# 2018_ACT_EXPANDER.net
KiCad netlist of a schematic drawn in Altium Designer
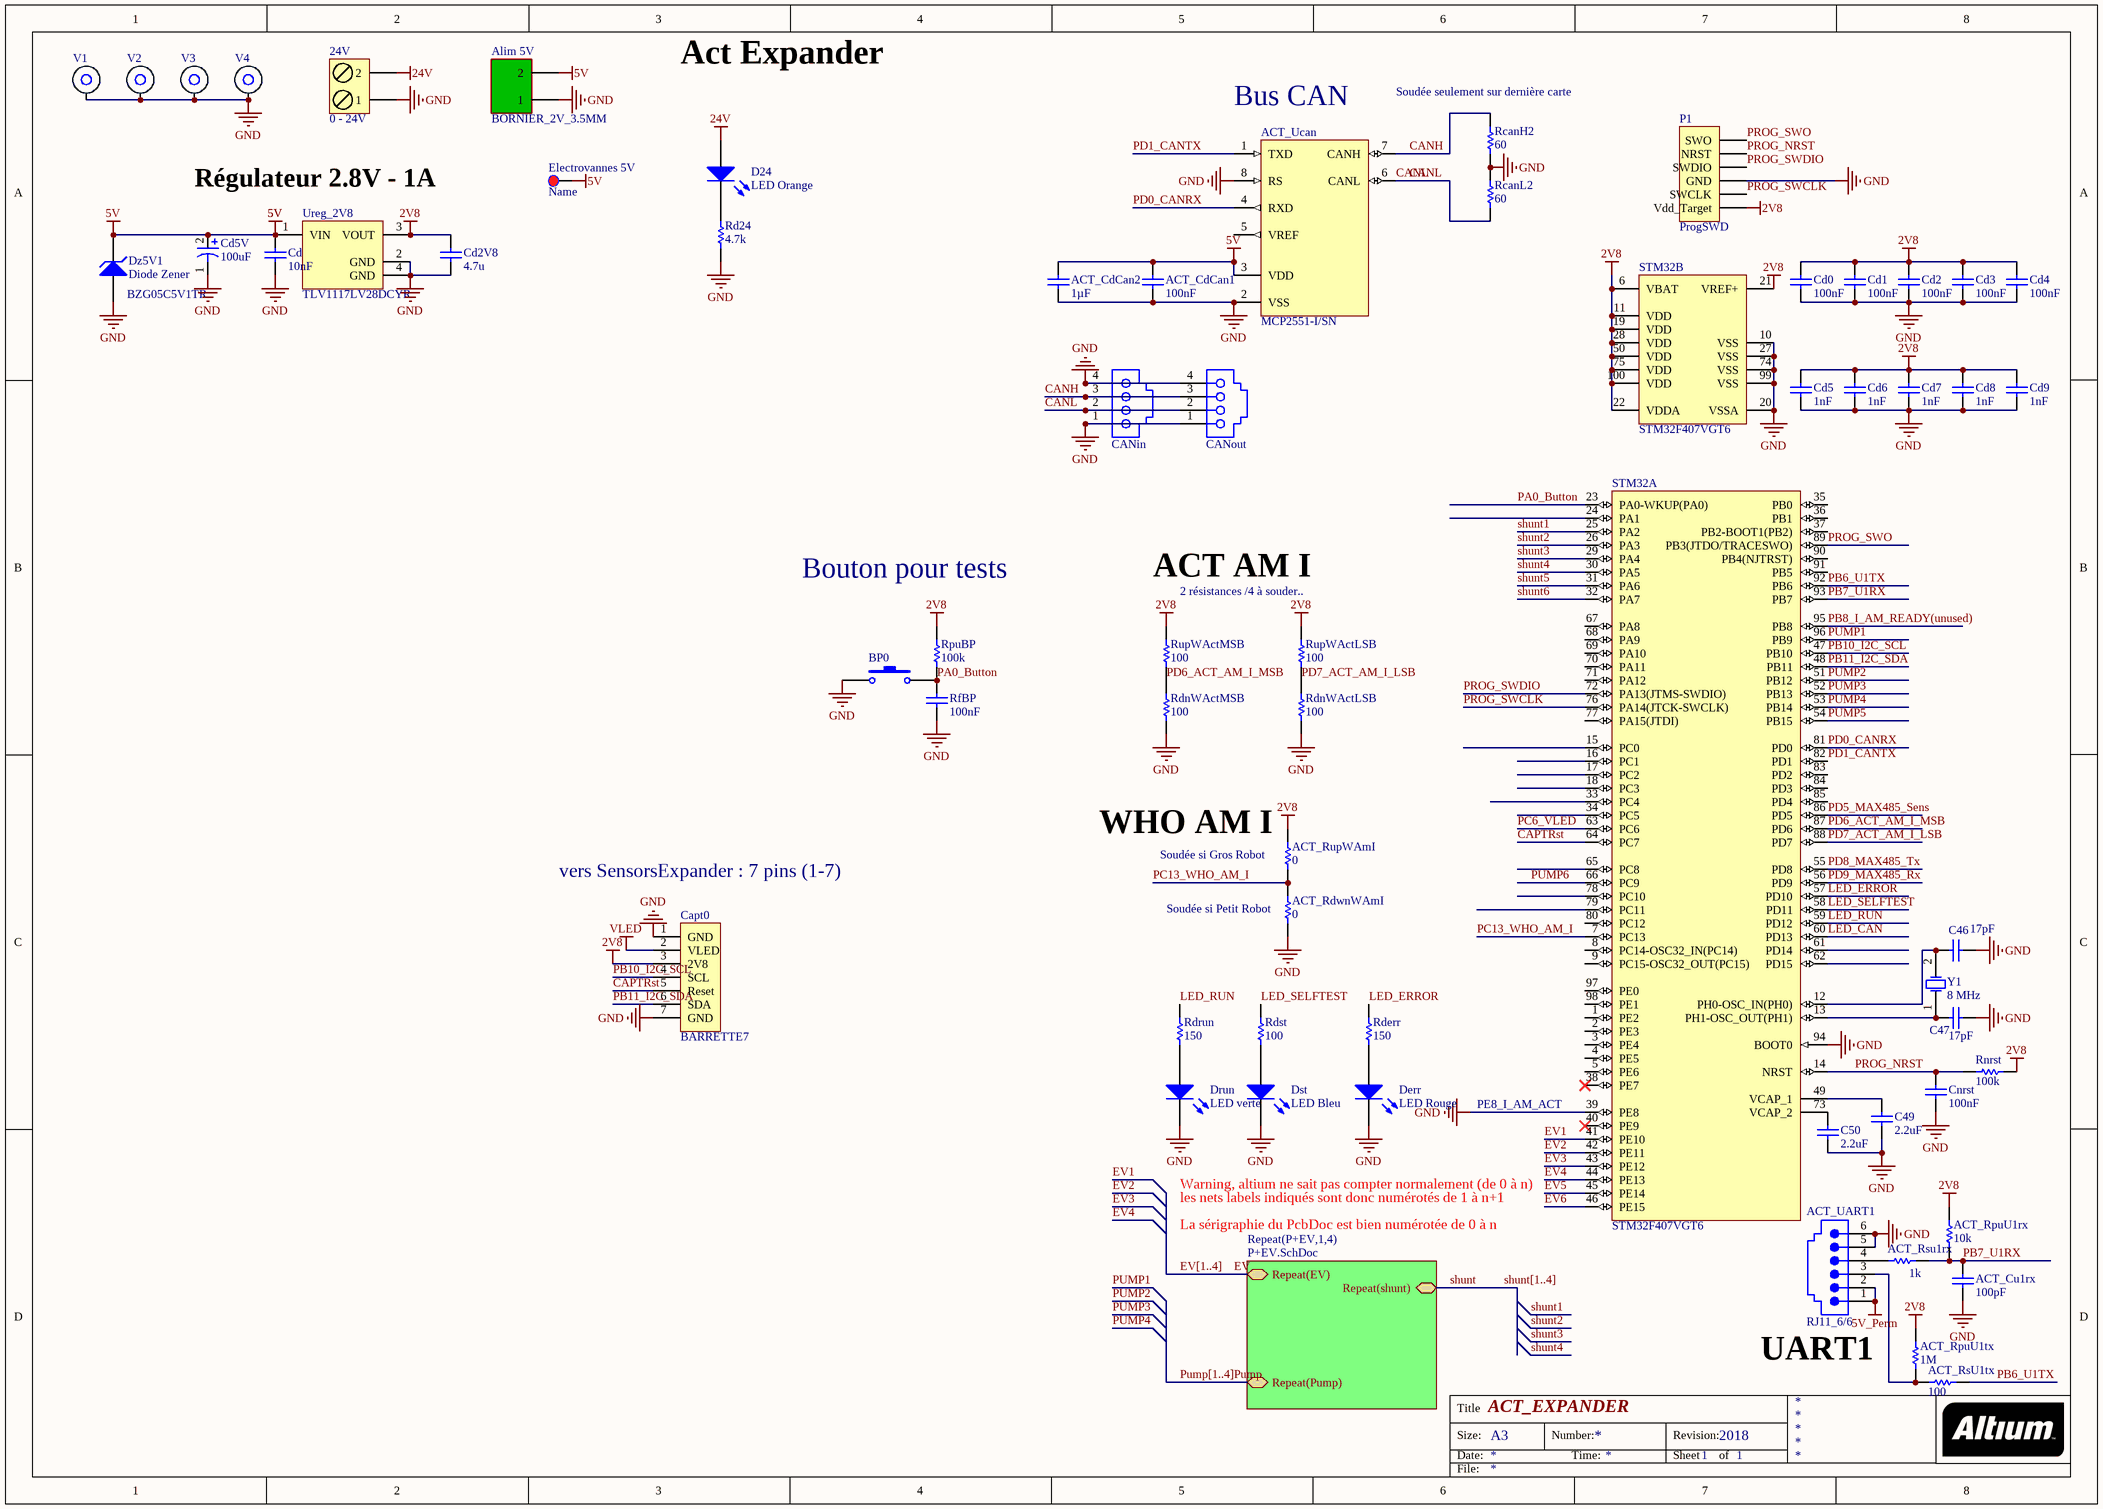
[diagram p0: 2018_ACT_EXPANDER.SchDoc]

(export (version "E")
  (design (tool "Eeschema 10.0.6"))
  (components
    (comp (ref "24V")
      (value "0 - 24V")
      (footprint "BORNIER2_FEM_COUDE")
      (description "Terminal blocks, 2 pins, pitch=5mm")
      (libsource (lib "miniprojet") (part "BORNIER2"))
    )
    (comp (ref "ACT_CdCan1")
      (value "100nF")
      (footprint "C0805_N")
      (description "Capacitor")
      (fields (field (name "PUBLISHER") "Altium Limited"))
      (libsource (lib "_ROBOT") (part "Condensateur"))
    )
    (comp (ref "ACT_CdCan2")
      (value "1µF")
      (footprint "C0805_N")
      (description "Capacitor")
      (fields (field (name "PUBLISHER") "Altium Limited"))
      (libsource (lib "_ROBOT") (part "Condensateur"))
    )
    (comp (ref "ACT_Cu1rx")
      (value "100pF")
      (footprint "C0805_N")
      (description "Capacitor")
      (fields (field (name "PUBLISHER") "Altium Limited"))
      (libsource (lib "_ROBOT") (part "Condensateur"))
    )
    (comp (ref "ACT_RdwnWAmI")
      (value "0")
      (footprint "R1206_N")
      (description "Resistor")
      (fields (field (name "PUBLISHER") "Altium Limited"))
      (libsource (lib "_ROBOT") (part "Resistor"))
    )
    (comp (ref "ACT_RpuU1rx")
      (value "10k")
      (footprint "R1206_N")
      (description "Resistor")
      (fields (field (name "PUBLISHER") "Altium Limited"))
      (libsource (lib "_ROBOT") (part "Resistor"))
    )
    (comp (ref "ACT_RpuU1tx")
      (value "1M")
      (footprint "R1206_N")
      (description "Resistor")
      (fields (field (name "PUBLISHER") "Altium Limited"))
      (libsource (lib "_ROBOT") (part "Resistor"))
    )
    (comp (ref "ACT_Rsu1rx")
      (value "1k")
      (footprint "R1206_N")
      (description "Resistor")
      (fields (field (name "PUBLISHER") "Altium Limited"))
      (libsource (lib "_ROBOT") (part "Resistor"))
    )
    (comp (ref "ACT_RsU1tx")
      (value "100")
      (footprint "R1206_N")
      (description "Resistor")
      (fields (field (name "PUBLISHER") "Altium Limited"))
      (libsource (lib "_ROBOT") (part "Resistor"))
    )
    (comp (ref "ACT_RupWAmI")
      (value "0")
      (footprint "R1206_N")
      (description "Resistor")
      (fields (field (name "PUBLISHER") "Altium Limited"))
      (libsource (lib "_ROBOT") (part "Resistor"))
    )
    (comp (ref "ACT_UART1")
      (value "RJ11_6/6")
      (footprint "RJ11_6/6 - droit")
      (description "Right Angle, Standard Profile, Offset Latch DECconnect, Flangeless PCB Jack")
      (fields (field (name "PUBLISHER") "Altium Limited"))
      (libsource (lib "Connecteur") (part "RJ11_6/6"))
    )
    (comp (ref "ACT_Ucan")
      (value "MCP2551-I/SN")
      (footprint "SO8_N")
      (description "High-Speed CAN Transceiver, 8-Pin SOIC, Industrial Temperature")
      (fields (field (name "PUBLISHER") "Damien Guitton"))
      (libsource (lib "Circuit intégré") (part "MCP2551-I/SN"))
    )
    (comp (ref "Alim 5V")
      (value "BORNIER_2V_3.5MM")
      (footprint "BORNIER_2V_3.5MM")
      (libsource (lib "Connecteur") (part "BORNIER_2V_3.5MM"))
    )
    (comp (ref "BP0")
      (value "SW_Pushbutton_6x6mm_Vertical")
      (footprint "Switch 6x6 Vertical")
      (description "Switch tactil 6mm x 6mm Vertical")
      (fields (field (name "PUBLISHER") "Damien Guitton"))
      (libsource (lib "_ROBOT") (part "SW_Pushbutton_6x6mm_Vertical"))
    )
    (comp (ref "C46")
      (value "17pF")
      (footprint "C0805_N")
      (description "Capacitor")
      (fields (field (name "PUBLISHER") "Altium Limited"))
      (libsource (lib "_ROBOT") (part "Condensateur"))
    )
    (comp (ref "C47")
      (value "17pF")
      (footprint "C0805_N")
      (description "Capacitor")
      (fields (field (name "PUBLISHER") "Altium Limited"))
      (libsource (lib "_ROBOT") (part "Condensateur"))
    )
    (comp (ref "C49")
      (value "2.2uF")
      (footprint "C0805_N")
      (description "Capacitor")
      (fields (field (name "PUBLISHER") "Altium Limited"))
      (libsource (lib "_ROBOT") (part "Condensateur"))
    )
    (comp (ref "C50")
      (value "2.2uF")
      (footprint "C0805_N")
      (description "Capacitor")
      (fields (field (name "PUBLISHER") "Altium Limited"))
      (libsource (lib "_ROBOT") (part "Condensateur"))
    )
    (comp (ref "CANin")
      (value "634104149621")
      (footprint "634104149621")
      (description "Modular Jack SMT Vertical Plastic 4P4C Top Entry WR-MJ")
      (fields (field (name "PUBLISHER") "Wurth Elektronik"))
      (libsource (lib "ALTIUM-MJ_VERTICAL_PLASTIC") (part "634104149621"))
    )
    (comp (ref "CANout")
      (value "634104149621")
      (footprint "634104149621")
      (description "Modular Jack SMT Vertical Plastic 4P4C Top Entry WR-MJ")
      (fields (field (name "PUBLISHER") "Wurth Elektronik"))
      (libsource (lib "ALTIUM-MJ_VERTICAL_PLASTIC") (part "634104149621"))
    )
    (comp (ref "Capt0")
      (value "BARRETTE7")
      (footprint "MOLEX7_2.50MM")
      (description "Header, 6-Pin")
      (fields (field (name "PUBLISHER") "Altium Limited"))
      (libsource (lib "Connecteur") (part "BARRETTE7"))
    )
    (comp (ref "Cd")
      (value "10nF")
      (footprint "C0805_N")
      (description "Capacitor")
      (fields (field (name "PUBLISHER") "Altium Limited"))
      (libsource (lib "_ROBOT") (part "Condensateur"))
    )
    (comp (ref "Cd0")
      (value "100nF")
      (footprint "C0805_N")
      (description "Capacitor")
      (fields (field (name "PUBLISHER") "Altium Limited"))
      (libsource (lib "_ROBOT") (part "Condensateur"))
    )
    (comp (ref "Cd1")
      (value "100nF")
      (footprint "C0805_N")
      (description "Capacitor")
      (fields (field (name "PUBLISHER") "Altium Limited"))
      (libsource (lib "_ROBOT") (part "Condensateur"))
    )
    (comp (ref "Cd2")
      (value "100nF")
      (footprint "C0805_N")
      (description "Capacitor")
      (fields (field (name "PUBLISHER") "Altium Limited"))
      (libsource (lib "_ROBOT") (part "Condensateur"))
    )
    (comp (ref "Cd2V8")
      (value "4.7u")
      (footprint "C1206_N")
      (description "Capacitor")
      (fields (field (name "PUBLISHER") "Altium Limited"))
      (libsource (lib "DG_Condensateur") (part "Capacitor"))
    )
    (comp (ref "Cd3")
      (value "100nF")
      (footprint "C0805_N")
      (description "Capacitor")
      (fields (field (name "PUBLISHER") "Altium Limited"))
      (libsource (lib "_ROBOT") (part "Condensateur"))
    )
    (comp (ref "Cd4")
      (value "100nF")
      (footprint "C0805_N")
      (description "Capacitor")
      (fields (field (name "PUBLISHER") "Altium Limited"))
      (libsource (lib "_ROBOT") (part "Condensateur"))
    )
    (comp (ref "Cd5")
      (value "1nF")
      (footprint "C0805_N")
      (description "Capacitor")
      (fields (field (name "PUBLISHER") "Altium Limited"))
      (libsource (lib "_ROBOT") (part "Condensateur"))
    )
    (comp (ref "Cd5V")
      (value "100uF")
      (footprint "CONDENSATEUR_POLARISE_ELECTROLYTIQUE_RADIAL_5.08/8.9")
      (description "Polarized Capacitor")
      (libsource (lib "_ROBOT") (part "Condensateur Polarise Traversant"))
    )
    (comp (ref "Cd6")
      (value "1nF")
      (footprint "C0805_N")
      (description "Capacitor")
      (fields (field (name "PUBLISHER") "Altium Limited"))
      (libsource (lib "_ROBOT") (part "Condensateur"))
    )
    (comp (ref "Cd7")
      (value "1nF")
      (footprint "C0805_N")
      (description "Capacitor")
      (fields (field (name "PUBLISHER") "Altium Limited"))
      (libsource (lib "_ROBOT") (part "Condensateur"))
    )
    (comp (ref "Cd8")
      (value "1nF")
      (footprint "C0805_N")
      (description "Capacitor")
      (fields (field (name "PUBLISHER") "Altium Limited"))
      (libsource (lib "_ROBOT") (part "Condensateur"))
    )
    (comp (ref "Cd9")
      (value "1nF")
      (footprint "C0805_N")
      (description "Capacitor")
      (fields (field (name "PUBLISHER") "Altium Limited"))
      (libsource (lib "_ROBOT") (part "Condensateur"))
    )
    (comp (ref "Cnrst")
      (value "100nF")
      (footprint "C0805_N")
      (description "Capacitor")
      (fields (field (name "PUBLISHER") "Altium Limited"))
      (libsource (lib "_ROBOT") (part "Condensateur"))
    )
    (comp (ref "D24")
      (value "LED Orange")
      (footprint "LED_0805")
      (description "Typical LED")
      (fields (field (name "PUBLISHER") "Altium Limited"))
      (libsource (lib "_ROBOT") (part "LED"))
    )
    (comp (ref "Derr")
      (value "LED Rouge")
      (footprint "LED_0805")
      (description "Typical LED")
      (fields (field (name "PUBLISHER") "Altium Limited"))
      (libsource (lib "_ROBOT") (part "LED"))
    )
    (comp (ref "Drun")
      (value "LED verte")
      (footprint "LED_0805")
      (description "Typical LED")
      (fields (field (name "PUBLISHER") "Altium Limited"))
      (libsource (lib "_ROBOT") (part "LED"))
    )
    (comp (ref "Dst")
      (value "LED Bleu")
      (footprint "LED_0805")
      (description "Typical LED")
      (fields (field (name "PUBLISHER") "Altium Limited"))
      (libsource (lib "_ROBOT") (part "LED"))
    )
    (comp (ref "Dz5V1")
      (value "Diode Zener")
      (footprint "SMA Diode")
      (description "Zener Diode")
      (fields (field (name "ALTIUM_UNNAMED_1") "BZG05C5V1TR"))
      (libsource (lib "_ROBOT") (part "Diode Zener"))
    )
    (comp (ref "Electrovannes 5V")
      (value "Name")
      (footprint "Point Test_D0.9_P0.5mm")
      (description "Point test")
      (fields (field (name "PUBLISHER") "Damien GUITTON"))
      (libsource (lib "Connecteur") (part "Point Test"))
    )
    (comp (ref "P1")
      (value "ProgSWD")
      (footprint "HDR1X6")
      (description "Header, 6-Pin")
      (fields (field (name "PUBLISHER") "Altium Limited"))
      (libsource (lib "DG_Connecteur") (part "Header 6"))
    )
    (comp (ref "RcanH2")
      (value "60")
      (footprint "R1206_N")
      (description "Resistor")
      (fields (field (name "PUBLISHER") "Altium Limited"))
      (libsource (lib "_ROBOT") (part "Resistor"))
    )
    (comp (ref "RcanL2")
      (value "60")
      (footprint "R1206_N")
      (description "Resistor")
      (fields (field (name "PUBLISHER") "Altium Limited"))
      (libsource (lib "_ROBOT") (part "Resistor"))
    )
    (comp (ref "Rd24")
      (value "4.7k")
      (footprint "R1206_N")
      (description "Resistor")
      (fields (field (name "PUBLISHER") "Altium Limited"))
      (libsource (lib "_ROBOT") (part "Resistor"))
    )
    (comp (ref "Rderr")
      (value "150")
      (footprint "R1206_N")
      (description "Resistor")
      (fields (field (name "PUBLISHER") "Altium Limited"))
      (libsource (lib "_ROBOT") (part "Resistor"))
    )
    (comp (ref "RdnWActLSB")
      (value "100")
      (footprint "R1206_N")
      (description "Resistor")
      (fields (field (name "PUBLISHER") "Altium Limited"))
      (libsource (lib "_ROBOT") (part "Resistor"))
    )
    (comp (ref "RdnWActMSB")
      (value "100")
      (footprint "R1206_N")
      (description "Resistor")
      (fields (field (name "PUBLISHER") "Altium Limited"))
      (libsource (lib "_ROBOT") (part "Resistor"))
    )
    (comp (ref "Rdrun")
      (value "150")
      (footprint "R1206_N")
      (description "Resistor")
      (fields (field (name "PUBLISHER") "Altium Limited"))
      (libsource (lib "_ROBOT") (part "Resistor"))
    )
    (comp (ref "Rdst")
      (value "100")
      (footprint "R1206_N")
      (description "Resistor")
      (fields (field (name "PUBLISHER") "Altium Limited"))
      (libsource (lib "_ROBOT") (part "Resistor"))
    )
    (comp (ref "RfBP")
      (value "100nF")
      (footprint "C0805_N")
      (description "Capacitor")
      (fields (field (name "PUBLISHER") "Altium Limited"))
      (libsource (lib "_ROBOT") (part "Condensateur"))
    )
    (comp (ref "Rnrst")
      (value "100k")
      (footprint "R1206_N")
      (description "Resistor")
      (fields (field (name "PUBLISHER") "Altium Limited"))
      (libsource (lib "_ROBOT") (part "Resistor"))
    )
    (comp (ref "RpuBP")
      (value "100k")
      (footprint "R1206_N")
      (description "Resistor")
      (fields (field (name "PUBLISHER") "Altium Limited"))
      (libsource (lib "_ROBOT") (part "Resistor"))
    )
    (comp (ref "RupWActLSB")
      (value "100")
      (footprint "R1206_N")
      (description "Resistor")
      (fields (field (name "PUBLISHER") "Altium Limited"))
      (libsource (lib "_ROBOT") (part "Resistor"))
    )
    (comp (ref "RupWActMSB")
      (value "100")
      (footprint "R1206_N")
      (description "Resistor")
      (fields (field (name "PUBLISHER") "Altium Limited"))
      (libsource (lib "_ROBOT") (part "Resistor"))
    )
    (comp (ref "STM32")
      (value "STM32F407VGT6")
      (footprint "STM-LQFP100_N")
      (fields (field (name "MANUFACTURER") "STMicroelectronics"))
      (libsource (lib "STMicroelectronics STM32 F4") (part "STM32F407VGT6"))
    )
    (comp (ref "Ureg_2V8")
      (value "TLV1117LV28DCYR")
      (footprint "SOT223-4N")
      (description "1000 mA, Low Voltage, Low Quiescent Current LDO Regulator, 3-Pin SOT-223, Extended Temperature")
      (fields (field (name "PUBLISHER") "Altium Limited"))
      (libsource (lib "Microchip Power Mgt Line Regulator") (part "MCP1826S-3302E/DB"))
    )
    (comp (ref "V1")
      (value "Entretoise WURTH CMS")
      (footprint "ENTRETOISE_CMS")
      (description "Entretoise Wurth")
      (fields (field (name "PUBLISHER") "Damien Guitton"))
      (libsource (lib "_ROBOT") (part "Entretoise WURTH CMS"))
    )
    (comp (ref "V2")
      (value "Entretoise WURTH CMS")
      (footprint "ENTRETOISE_CMS")
      (description "Entretoise Wurth")
      (fields (field (name "PUBLISHER") "Damien Guitton"))
      (libsource (lib "_ROBOT") (part "Entretoise WURTH CMS"))
    )
    (comp (ref "V3")
      (value "Entretoise WURTH CMS")
      (footprint "ENTRETOISE_CMS")
      (description "Entretoise Wurth")
      (fields (field (name "PUBLISHER") "Damien Guitton"))
      (libsource (lib "_ROBOT") (part "Entretoise WURTH CMS"))
    )
    (comp (ref "V4")
      (value "Entretoise WURTH CMS")
      (footprint "ENTRETOISE_CMS")
      (description "Entretoise Wurth")
      (fields (field (name "PUBLISHER") "Damien Guitton"))
      (libsource (lib "_ROBOT") (part "Entretoise WURTH CMS"))
    )
    (comp (ref "Y1")
      (value "8 MHz")
      (footprint "HC49/4H_SMX")
      (description "Crystal Oscillator")
      (fields (field (name "PUBLISHER") "Altium Limited"))
      (libsource (lib "_ROBOT") (part "Quartz"))
    )
  )
  (nets
    (net (code "5") (name "/CANH") (class "Default")
      (node (ref "ACT_Ucan") (pin "7") (pinfunction "CANH_7") (pintype "bidirectional"))
      (node (ref "CANin") (pin "3") (pinfunction "3_3") (pintype "passive"))
      (node (ref "CANout") (pin "3") (pinfunction "3_3") (pintype "passive"))
      (node (ref "RcanH2") (pin "1") (pinfunction "1_1") (pintype "passive"))
    )
    (net (code "6") (name "/CANL") (class "Default")
      (node (ref "ACT_Ucan") (pin "6") (pinfunction "CANL_6") (pintype "bidirectional"))
      (node (ref "CANin") (pin "2") (pinfunction "2_2") (pintype "passive"))
      (node (ref "CANout") (pin "2") (pinfunction "2_2") (pintype "passive"))
      (node (ref "RcanL2") (pin "1") (pinfunction "1_1") (pintype "passive"))
    )
    (net (code "7") (name "/CAPTRst") (class "Default")
      (node (ref "Capt0") (pin "5") (pinfunction "Reset_5") (pintype "passive"))
      (node (ref "STM32") (pin "64") (pinfunction "PC7_64") (pintype "bidirectional"))
    )
    (net (code "9") (name "/EV1") (class "Default")
      (node (ref "STM32") (pin "41") (pinfunction "PE10_41") (pintype "bidirectional"))
    )
    (net (code "10") (name "/EV2") (class "Default")
      (node (ref "STM32") (pin "42") (pinfunction "PE11_42") (pintype "bidirectional"))
    )
    (net (code "11") (name "/EV3") (class "Default")
      (node (ref "STM32") (pin "43") (pinfunction "PE12_43") (pintype "bidirectional"))
    )
    (net (code "12") (name "/EV4") (class "Default")
      (node (ref "STM32") (pin "44") (pinfunction "PE13_44") (pintype "bidirectional"))
    )
    (net (code "13") (name "/EV5") (class "Default")
      (node (ref "STM32") (pin "45") (pinfunction "PE14_45") (pintype "bidirectional"))
    )
    (net (code "14") (name "/EV6") (class "Default")
      (node (ref "STM32") (pin "46") (pinfunction "PE15_46") (pintype "bidirectional"))
    )
    (net (code "16") (name "/LED_CAN") (class "Default")
      (node (ref "STM32") (pin "60") (pinfunction "PD13_60") (pintype "bidirectional"))
    )
    (net (code "17") (name "/LED_ERROR") (class "Default")
      (node (ref "Rderr") (pin "1") (pinfunction "1_1") (pintype "passive"))
      (node (ref "STM32") (pin "57") (pinfunction "PD10_57") (pintype "bidirectional"))
    )
    (net (code "18") (name "/LED_RUN") (class "Default")
      (node (ref "Rdrun") (pin "1") (pinfunction "1_1") (pintype "passive"))
      (node (ref "STM32") (pin "59") (pinfunction "PD12_59") (pintype "bidirectional"))
    )
    (net (code "19") (name "/LED_SELFTEST") (class "Default")
      (node (ref "Rdst") (pin "1") (pinfunction "1_1") (pintype "passive"))
      (node (ref "STM32") (pin "58") (pinfunction "PD11_58") (pintype "bidirectional"))
    )
    (net (code "20") (name "/PA0_Button") (class "Default")
      (node (ref "BP0") (pin "3") (pinfunction "3_3") (pintype "passive"))
      (node (ref "RfBP") (pin "2") (pinfunction "2_2") (pintype "passive"))
      (node (ref "RpuBP") (pin "2") (pinfunction "2_2") (pintype "passive"))
      (node (ref "STM32") (pin "23") (pinfunction "PA0-WKUP(PA0)_23") (pintype "bidirectional"))
    )
    (net (code "21") (name "/PB6_U1TX") (class "Default")
      (node (ref "ACT_RsU1tx") (pin "2") (pinfunction "2_2") (pintype "passive"))
      (node (ref "STM32") (pin "92") (pinfunction "PB6_92") (pintype "bidirectional"))
    )
    (net (code "22") (name "/PB7_U1RX") (class "Default")
      (node (ref "ACT_Cu1rx") (pin "2") (pinfunction "2_2") (pintype "passive"))
      (node (ref "ACT_RpuU1rx") (pin "1") (pinfunction "1_1") (pintype "passive"))
      (node (ref "ACT_Rsu1rx") (pin "1") (pinfunction "1_1") (pintype "passive"))
      (node (ref "STM32") (pin "93") (pinfunction "PB7_93") (pintype "bidirectional"))
    )
    (net (code "23") (name "/PB8_I_AM_READY(unused)") (class "Default")
      (node (ref "STM32") (pin "95") (pinfunction "PB8_95") (pintype "bidirectional"))
    )
    (net (code "24") (name "/PB10_I2C_SCL") (class "Default")
      (node (ref "Capt0") (pin "4") (pinfunction "SCL_4") (pintype "passive"))
      (node (ref "STM32") (pin "47") (pinfunction "PB10_47") (pintype "bidirectional"))
    )
    (net (code "25") (name "/PB11_I2C_SDA") (class "Default")
      (node (ref "Capt0") (pin "6") (pinfunction "SDA_6") (pintype "passive"))
      (node (ref "STM32") (pin "48") (pinfunction "PB11_48") (pintype "bidirectional"))
    )
    (net (code "26") (name "/PC6_VLED") (class "Default")
      (node (ref "STM32") (pin "63") (pinfunction "PC6_63") (pintype "bidirectional"))
    )
    (net (code "27") (name "/PC13_WHO_AM_I") (class "Default")
      (node (ref "ACT_RdwnWAmI") (pin "2") (pinfunction "2_2") (pintype "passive"))
      (node (ref "ACT_RupWAmI") (pin "1") (pinfunction "1_1") (pintype "passive"))
      (node (ref "STM32") (pin "7") (pinfunction "PC13_7") (pintype "bidirectional"))
    )
    (net (code "28") (name "/PD0_CANRX") (class "Default")
      (node (ref "ACT_Ucan") (pin "4") (pinfunction "RXD_4") (pintype "output"))
      (node (ref "STM32") (pin "81") (pinfunction "PD0_81") (pintype "bidirectional"))
    )
    (net (code "29") (name "/PD1_CANTX") (class "Default")
      (node (ref "ACT_Ucan") (pin "1") (pinfunction "TXD_1") (pintype "input"))
      (node (ref "STM32") (pin "82") (pinfunction "PD1_82") (pintype "bidirectional"))
    )
    (net (code "30") (name "/PD5_MAX485_Sens") (class "Default")
      (node (ref "STM32") (pin "86") (pinfunction "PD5_86") (pintype "bidirectional"))
    )
    (net (code "31") (name "/PD6_ACT_AM_I_MSB") (class "Default")
      (node (ref "RdnWActMSB") (pin "2") (pinfunction "2_2") (pintype "passive"))
      (node (ref "RupWActMSB") (pin "1") (pinfunction "1_1") (pintype "passive"))
      (node (ref "STM32") (pin "87") (pinfunction "PD6_87") (pintype "bidirectional"))
    )
    (net (code "32") (name "/PD7_ACT_AM_I_LSB") (class "Default")
      (node (ref "RdnWActLSB") (pin "2") (pinfunction "2_2") (pintype "passive"))
      (node (ref "RupWActLSB") (pin "1") (pinfunction "1_1") (pintype "passive"))
      (node (ref "STM32") (pin "88") (pinfunction "PD7_88") (pintype "bidirectional"))
    )
    (net (code "33") (name "/PD8_MAX485_Tx") (class "Default")
      (node (ref "STM32") (pin "55") (pinfunction "PD8_55") (pintype "bidirectional"))
    )
    (net (code "34") (name "/PD9_MAX485_Rx") (class "Default")
      (node (ref "STM32") (pin "56") (pinfunction "PD9_56") (pintype "bidirectional"))
    )
    (net (code "35") (name "/PROG_NRST") (class "Default")
      (node (ref "Cnrst") (pin "2") (pinfunction "2_2") (pintype "passive"))
      (node (ref "P1") (pin "5") (pinfunction "NRST_5") (pintype "passive"))
      (node (ref "Rnrst") (pin "1") (pinfunction "1_1") (pintype "passive"))
      (node (ref "STM32") (pin "14") (pinfunction "NRST_14") (pintype "bidirectional"))
    )
    (net (code "36") (name "/PROG_SWCLK") (class "Default")
      (node (ref "P1") (pin "2") (pinfunction "SWCLK_2") (pintype "passive"))
      (node (ref "STM32") (pin "76") (pinfunction "PA14(JTCK-SWCLK)_76") (pintype "bidirectional"))
    )
    (net (code "37") (name "/PROG_SWDIO") (class "Default")
      (node (ref "P1") (pin "4") (pinfunction "SWDIO_4") (pintype "passive"))
      (node (ref "STM32") (pin "72") (pinfunction "PA13(JTMS-SWDIO)_72") (pintype "bidirectional"))
    )
    (net (code "38") (name "/PROG_SWO") (class "Default")
      (node (ref "P1") (pin "6") (pinfunction "SWO_6") (pintype "passive"))
      (node (ref "STM32") (pin "89") (pinfunction "PB3(JTDO/TRACESWO)_89") (pintype "bidirectional"))
    )
    (net (code "39") (name "/PUMP1") (class "Default")
      (node (ref "STM32") (pin "96") (pinfunction "PB9_96") (pintype "bidirectional"))
    )
    (net (code "40") (name "/PUMP2") (class "Default")
      (node (ref "STM32") (pin "51") (pinfunction "PB12_51") (pintype "bidirectional"))
    )
    (net (code "41") (name "/PUMP3") (class "Default")
      (node (ref "STM32") (pin "52") (pinfunction "PB13_52") (pintype "bidirectional"))
    )
    (net (code "42") (name "/PUMP4") (class "Default")
      (node (ref "STM32") (pin "53") (pinfunction "PB14_53") (pintype "bidirectional"))
    )
    (net (code "43") (name "/PUMP5") (class "Default")
      (node (ref "STM32") (pin "54") (pinfunction "PB15_54") (pintype "bidirectional"))
    )
    (net (code "44") (name "/PUMP6") (class "Default")
      (node (ref "STM32") (pin "66") (pinfunction "PC9_66") (pintype "bidirectional"))
    )
    (net (code "48") (name "/shunt1") (class "Default")
      (node (ref "STM32") (pin "25") (pinfunction "PA2_25") (pintype "bidirectional"))
    )
    (net (code "49") (name "/shunt2") (class "Default")
      (node (ref "STM32") (pin "26") (pinfunction "PA3_26") (pintype "bidirectional"))
    )
    (net (code "50") (name "/shunt3") (class "Default")
      (node (ref "STM32") (pin "29") (pinfunction "PA4_29") (pintype "bidirectional"))
    )
    (net (code "51") (name "/shunt4") (class "Default")
      (node (ref "STM32") (pin "30") (pinfunction "PA5_30") (pintype "bidirectional"))
    )
    (net (code "52") (name "/shunt5") (class "Default")
      (node (ref "STM32") (pin "31") (pinfunction "PA6_31") (pintype "bidirectional"))
    )
    (net (code "53") (name "/shunt6") (class "Default")
      (node (ref "STM32") (pin "32") (pinfunction "PA7_32") (pintype "bidirectional"))
    )
    (net (code "55") (name "2V8") (class "Default")
      (node (ref "ACT_RpuU1rx") (pin "2") (pinfunction "2_2") (pintype "passive"))
      (node (ref "ACT_RpuU1tx") (pin "2") (pinfunction "2_2") (pintype "passive"))
      (node (ref "ACT_RupWAmI") (pin "2") (pinfunction "2_2") (pintype "passive"))
      (node (ref "Capt0") (pin "3") (pinfunction "2V8_3") (pintype "passive"))
      (node (ref "Cd0") (pin "2") (pinfunction "2_2") (pintype "passive"))
      (node (ref "Cd1") (pin "2") (pinfunction "2_2") (pintype "passive"))
      (node (ref "Cd2") (pin "2") (pinfunction "2_2") (pintype "passive"))
      (node (ref "Cd2V8") (pin "2") (pinfunction "2_2") (pintype "passive"))
      (node (ref "Cd3") (pin "2") (pinfunction "2_2") (pintype "passive"))
      (node (ref "Cd4") (pin "2") (pinfunction "2_2") (pintype "passive"))
      (node (ref "Cd5") (pin "2") (pinfunction "2_2") (pintype "passive"))
      (node (ref "Cd6") (pin "2") (pinfunction "2_2") (pintype "passive"))
      (node (ref "Cd7") (pin "2") (pinfunction "2_2") (pintype "passive"))
      (node (ref "Cd8") (pin "2") (pinfunction "2_2") (pintype "passive"))
      (node (ref "Cd9") (pin "2") (pinfunction "2_2") (pintype "passive"))
      (node (ref "P1") (pin "1") (pinfunction "Vdd_Target_1") (pintype "passive"))
      (node (ref "Rnrst") (pin "2") (pinfunction "2_2") (pintype "passive"))
      (node (ref "RpuBP") (pin "1") (pinfunction "1_1") (pintype "passive"))
      (node (ref "RupWActLSB") (pin "2") (pinfunction "2_2") (pintype "passive"))
      (node (ref "RupWActMSB") (pin "2") (pinfunction "2_2") (pintype "passive"))
      (node (ref "STM32") (pin "100") (pinfunction "VDD_100") (pintype "power_in"))
      (node (ref "STM32") (pin "11") (pinfunction "VDD_11") (pintype "power_in"))
      (node (ref "STM32") (pin "19") (pinfunction "VDD_19") (pintype "power_in"))
      (node (ref "STM32") (pin "21") (pinfunction "VREF+_21") (pintype "power_in"))
      (node (ref "STM32") (pin "22") (pinfunction "VDDA_22") (pintype "power_in"))
      (node (ref "STM32") (pin "28") (pinfunction "VDD_28") (pintype "power_in"))
      (node (ref "STM32") (pin "50") (pinfunction "VDD_50") (pintype "power_in"))
      (node (ref "STM32") (pin "6") (pinfunction "VBAT_6") (pintype "power_in"))
      (node (ref "STM32") (pin "75") (pinfunction "VDD_75") (pintype "power_in"))
      (node (ref "Ureg_2V8") (pin "3") (pinfunction "VOUT_3") (pintype "power_in"))
    )
    (net (code "56") (name "5V") (class "Default")
      (node (ref "ACT_CdCan1") (pin "2") (pinfunction "2_2") (pintype "passive"))
      (node (ref "ACT_CdCan2") (pin "2") (pinfunction "2_2") (pintype "passive"))
      (node (ref "ACT_Ucan") (pin "3") (pinfunction "VDD_3") (pintype "power_in"))
      (node (ref "Alim 5V") (pin "2") (pinfunction "2_2") (pintype "passive"))
      (node (ref "Cd") (pin "2") (pinfunction "2_2") (pintype "passive"))
      (node (ref "Cd5V") (pin "2") (pinfunction "2_2") (pintype "passive"))
      (node (ref "Dz5V1") (pin "2") (pinfunction "K_2") (pintype "passive"))
      (node (ref "Electrovannes 5V") (pin "1") (pinfunction "1_1") (pintype "passive"))
      (node (ref "Ureg_2V8") (pin "1") (pinfunction "VIN_1") (pintype "power_in"))
    )
    (net (code "57") (name "5V_Perm") (class "Default")
      (node (ref "ACT_UART1") (pin "1") (pinfunction "1_1") (pintype "passive"))
      (node (ref "ACT_UART1") (pin "2") (pinfunction "2_2") (pintype "passive"))
    )
    (net (code "58") (name "24V") (class "Default")
      (node (ref "24V") (pin "2") (pinfunction "2_2") (pintype "passive"))
      (node (ref "D24") (pin "1") (pinfunction "A_1") (pintype "passive"))
    )
    (net (code "59") (name "GND") (class "Default")
      (node (ref "24V") (pin "1") (pinfunction "1_1") (pintype "passive"))
      (node (ref "ACT_CdCan1") (pin "1") (pinfunction "1_1") (pintype "passive"))
      (node (ref "ACT_CdCan2") (pin "1") (pinfunction "1_1") (pintype "passive"))
      (node (ref "ACT_Cu1rx") (pin "1") (pinfunction "1_1") (pintype "passive"))
      (node (ref "ACT_RdwnWAmI") (pin "1") (pinfunction "1_1") (pintype "passive"))
      (node (ref "ACT_UART1") (pin "5") (pinfunction "5_5") (pintype "passive"))
      (node (ref "ACT_UART1") (pin "6") (pinfunction "6_6") (pintype "passive"))
      (node (ref "ACT_Ucan") (pin "2") (pinfunction "VSS_2") (pintype "power_in"))
      (node (ref "ACT_Ucan") (pin "8") (pinfunction "RS_8") (pintype "input"))
      (node (ref "Alim 5V") (pin "1") (pinfunction "1_1") (pintype "passive"))
      (node (ref "BP0") (pin "1") (pinfunction "1_1") (pintype "passive"))
      (node (ref "C46") (pin "1") (pinfunction "1_1") (pintype "passive"))
      (node (ref "C47") (pin "1") (pinfunction "1_1") (pintype "passive"))
      (node (ref "C49") (pin "1") (pinfunction "1_1") (pintype "passive"))
      (node (ref "C50") (pin "1") (pinfunction "1_1") (pintype "passive"))
      (node (ref "CANin") (pin "1") (pinfunction "1_1") (pintype "passive"))
      (node (ref "CANin") (pin "4") (pinfunction "4_4") (pintype "passive"))
      (node (ref "CANout") (pin "1") (pinfunction "1_1") (pintype "passive"))
      (node (ref "CANout") (pin "4") (pinfunction "4_4") (pintype "passive"))
      (node (ref "Capt0") (pin "1") (pinfunction "GND_1") (pintype "passive"))
      (node (ref "Capt0") (pin "7") (pinfunction "GND_7") (pintype "passive"))
      (node (ref "Cd") (pin "1") (pinfunction "1_1") (pintype "passive"))
      (node (ref "Cd0") (pin "1") (pinfunction "1_1") (pintype "passive"))
      (node (ref "Cd1") (pin "1") (pinfunction "1_1") (pintype "passive"))
      (node (ref "Cd2") (pin "1") (pinfunction "1_1") (pintype "passive"))
      (node (ref "Cd2V8") (pin "1") (pinfunction "1_1") (pintype "passive"))
      (node (ref "Cd3") (pin "1") (pinfunction "1_1") (pintype "passive"))
      (node (ref "Cd4") (pin "1") (pinfunction "1_1") (pintype "passive"))
      (node (ref "Cd5") (pin "1") (pinfunction "1_1") (pintype "passive"))
      (node (ref "Cd5V") (pin "1") (pinfunction "1_1") (pintype "passive"))
      (node (ref "Cd6") (pin "1") (pinfunction "1_1") (pintype "passive"))
      (node (ref "Cd7") (pin "1") (pinfunction "1_1") (pintype "passive"))
      (node (ref "Cd8") (pin "1") (pinfunction "1_1") (pintype "passive"))
      (node (ref "Cd9") (pin "1") (pinfunction "1_1") (pintype "passive"))
      (node (ref "Cnrst") (pin "1") (pinfunction "1_1") (pintype "passive"))
      (node (ref "Derr") (pin "2") (pinfunction "K_2") (pintype "passive"))
      (node (ref "Drun") (pin "2") (pinfunction "K_2") (pintype "passive"))
      (node (ref "Dst") (pin "2") (pinfunction "K_2") (pintype "passive"))
      (node (ref "Dz5V1") (pin "1") (pinfunction "A_1") (pintype "passive"))
      (node (ref "P1") (pin "3") (pinfunction "GND_3") (pintype "passive"))
      (node (ref "RcanH2") (pin "2") (pinfunction "2_2") (pintype "passive"))
      (node (ref "RcanL2") (pin "2") (pinfunction "2_2") (pintype "passive"))
      (node (ref "Rd24") (pin "2") (pinfunction "2_2") (pintype "passive"))
      (node (ref "RdnWActLSB") (pin "1") (pinfunction "1_1") (pintype "passive"))
      (node (ref "RdnWActMSB") (pin "1") (pinfunction "1_1") (pintype "passive"))
      (node (ref "RfBP") (pin "1") (pinfunction "1_1") (pintype "passive"))
      (node (ref "STM32") (pin "10") (pinfunction "VSS_10") (pintype "power_in"))
      (node (ref "STM32") (pin "20") (pinfunction "VSSA_20") (pintype "power_in"))
      (node (ref "STM32") (pin "27") (pinfunction "VSS_27") (pintype "power_in"))
      (node (ref "STM32") (pin "39") (pinfunction "PE8_39") (pintype "bidirectional"))
      (node (ref "STM32") (pin "74") (pinfunction "VSS_74") (pintype "power_in"))
      (node (ref "STM32") (pin "94") (pinfunction "BOOT0_94") (pintype "input"))
      (node (ref "STM32") (pin "99") (pinfunction "VSS_99") (pintype "power_in"))
      (node (ref "Ureg_2V8") (pin "2") (pinfunction "GND_2") (pintype "power_in"))
      (node (ref "Ureg_2V8") (pin "4") (pinfunction "GND_4") (pintype "power_in"))
      (node (ref "V1") (pin "1") (pinfunction "1_1") (pintype "passive"))
      (node (ref "V2") (pin "1") (pinfunction "1_1") (pintype "passive"))
      (node (ref "V3") (pin "1") (pinfunction "1_1") (pintype "passive"))
      (node (ref "V4") (pin "1") (pinfunction "1_1") (pintype "passive"))
    )
    (net (code "60") (name "Net-(ACT_RpuU1tx-Pad1)") (class "Default")
      (node (ref "ACT_RpuU1tx") (pin "1") (pinfunction "1_1") (pintype "passive"))
      (node (ref "ACT_RsU1tx") (pin "1") (pinfunction "1_1") (pintype "passive"))
      (node (ref "ACT_UART1") (pin "3") (pinfunction "3_3") (pintype "passive"))
    )
    (net (code "61") (name "Net-(ACT_Rsu1rx-Pad2)") (class "Default")
      (node (ref "ACT_Rsu1rx") (pin "2") (pinfunction "2_2") (pintype "passive"))
      (node (ref "ACT_UART1") (pin "4") (pinfunction "4_4") (pintype "passive"))
    )
    (net (code "62") (name "Net-(D24-K)") (class "Default")
      (node (ref "D24") (pin "2") (pinfunction "K_2") (pintype "passive"))
      (node (ref "Rd24") (pin "1") (pinfunction "1_1") (pintype "passive"))
    )
    (net (code "63") (name "Net-(Derr-A)") (class "Default")
      (node (ref "Derr") (pin "1") (pinfunction "A_1") (pintype "passive"))
      (node (ref "Rderr") (pin "2") (pinfunction "2_2") (pintype "passive"))
    )
    (net (code "64") (name "Net-(Drun-A)") (class "Default")
      (node (ref "Drun") (pin "1") (pinfunction "A_1") (pintype "passive"))
      (node (ref "Rdrun") (pin "2") (pinfunction "2_2") (pintype "passive"))
    )
    (net (code "65") (name "Net-(Dst-A)") (class "Default")
      (node (ref "Dst") (pin "1") (pinfunction "A_1") (pintype "passive"))
      (node (ref "Rdst") (pin "2") (pinfunction "2_2") (pintype "passive"))
    )
    (net (code "66") (name "Net-(STM32A-PH0-OSC_IN(PH0))") (class "Default")
      (node (ref "C46") (pin "2") (pinfunction "2_2") (pintype "passive"))
      (node (ref "STM32") (pin "12") (pinfunction "PH0-OSC_IN(PH0)_12") (pintype "bidirectional"))
      (node (ref "Y1") (pin "2") (pinfunction "OSC2_2") (pintype "passive"))
    )
    (net (code "67") (name "Net-(STM32A-PH1-OSC_OUT(PH1))") (class "Default")
      (node (ref "C47") (pin "2") (pinfunction "2_2") (pintype "passive"))
      (node (ref "STM32") (pin "13") (pinfunction "PH1-OSC_OUT(PH1)_13") (pintype "bidirectional"))
      (node (ref "Y1") (pin "1") (pinfunction "OSC1_1") (pintype "passive"))
    )
    (net (code "68") (name "Net-(STM32A-VCAP_1)") (class "Default")
      (node (ref "C49") (pin "2") (pinfunction "2_2") (pintype "passive"))
      (node (ref "STM32") (pin "49") (pinfunction "VCAP_1_49") (pintype "power_in"))
    )
    (net (code "69") (name "Net-(STM32A-VCAP_2)") (class "Default")
      (node (ref "C50") (pin "2") (pinfunction "2_2") (pintype "passive"))
      (node (ref "STM32") (pin "73") (pinfunction "VCAP_2_73") (pintype "power_in"))
    )
    (net (code "70") (name "VLED") (class "Default")
      (node (ref "Capt0") (pin "2") (pinfunction "VLED_2") (pintype "passive"))
    )
    (net (code "71") (name "unconnected-(ACT_Ucan-VREF-Pad5)") (class "Default")
      (node (ref "ACT_Ucan") (pin "5") (pinfunction "VREF_5") (pintype "output"))
    )
    (net (code "72") (name "unconnected-(STM32A-PA1-Pad24)") (class "Default")
      (node (ref "STM32") (pin "24") (pinfunction "PA1_24") (pintype "bidirectional"))
    )
    (net (code "73") (name "unconnected-(STM32A-PA8-Pad67)") (class "Default")
      (node (ref "STM32") (pin "67") (pinfunction "PA8_67") (pintype "bidirectional"))
    )
    (net (code "74") (name "unconnected-(STM32A-PA9-Pad68)") (class "Default")
      (node (ref "STM32") (pin "68") (pinfunction "PA9_68") (pintype "bidirectional"))
    )
    (net (code "75") (name "unconnected-(STM32A-PA10-Pad69)") (class "Default")
      (node (ref "STM32") (pin "69") (pinfunction "PA10_69") (pintype "bidirectional"))
    )
    (net (code "76") (name "unconnected-(STM32A-PA11-Pad70)") (class "Default")
      (node (ref "STM32") (pin "70") (pinfunction "PA11_70") (pintype "bidirectional"))
    )
    (net (code "77") (name "unconnected-(STM32A-PA12-Pad71)") (class "Default")
      (node (ref "STM32") (pin "71") (pinfunction "PA12_71") (pintype "bidirectional"))
    )
    (net (code "78") (name "unconnected-(STM32A-PA15(JTDI)-Pad77)") (class "Default")
      (node (ref "STM32") (pin "77") (pinfunction "PA15(JTDI)_77") (pintype "bidirectional"))
    )
    (net (code "79") (name "unconnected-(STM32A-PB0-Pad35)") (class "Default")
      (node (ref "STM32") (pin "35") (pinfunction "PB0_35") (pintype "bidirectional"))
    )
    (net (code "80") (name "unconnected-(STM32A-PB1-Pad36)") (class "Default")
      (node (ref "STM32") (pin "36") (pinfunction "PB1_36") (pintype "bidirectional"))
    )
    (net (code "81") (name "unconnected-(STM32A-PB2-BOOT1(PB2)-Pad37)") (class "Default")
      (node (ref "STM32") (pin "37") (pinfunction "PB2-BOOT1(PB2)_37") (pintype "bidirectional"))
    )
    (net (code "82") (name "unconnected-(STM32A-PB4(NJTRST)-Pad90)") (class "Default")
      (node (ref "STM32") (pin "90") (pinfunction "PB4(NJTRST)_90") (pintype "bidirectional"))
    )
    (net (code "83") (name "unconnected-(STM32A-PB5-Pad91)") (class "Default")
      (node (ref "STM32") (pin "91") (pinfunction "PB5_91") (pintype "bidirectional"))
    )
    (net (code "84") (name "unconnected-(STM32A-PC0-Pad15)") (class "Default")
      (node (ref "STM32") (pin "15") (pinfunction "PC0_15") (pintype "bidirectional"))
    )
    (net (code "85") (name "unconnected-(STM32A-PC1-Pad16)") (class "Default")
      (node (ref "STM32") (pin "16") (pinfunction "PC1_16") (pintype "bidirectional"))
    )
    (net (code "86") (name "unconnected-(STM32A-PC2-Pad17)") (class "Default")
      (node (ref "STM32") (pin "17") (pinfunction "PC2_17") (pintype "bidirectional"))
    )
    (net (code "87") (name "unconnected-(STM32A-PC3-Pad18)") (class "Default")
      (node (ref "STM32") (pin "18") (pinfunction "PC3_18") (pintype "bidirectional"))
    )
    (net (code "88") (name "unconnected-(STM32A-PC4-Pad33)") (class "Default")
      (node (ref "STM32") (pin "33") (pinfunction "PC4_33") (pintype "bidirectional"))
    )
    (net (code "89") (name "unconnected-(STM32A-PC5-Pad34)") (class "Default")
      (node (ref "STM32") (pin "34") (pinfunction "PC5_34") (pintype "bidirectional"))
    )
    (net (code "90") (name "unconnected-(STM32A-PC8-Pad65)") (class "Default")
      (node (ref "STM32") (pin "65") (pinfunction "PC8_65") (pintype "bidirectional"))
    )
    (net (code "91") (name "unconnected-(STM32A-PC10-Pad78)") (class "Default")
      (node (ref "STM32") (pin "78") (pinfunction "PC10_78") (pintype "bidirectional"))
    )
    (net (code "92") (name "unconnected-(STM32A-PC11-Pad79)") (class "Default")
      (node (ref "STM32") (pin "79") (pinfunction "PC11_79") (pintype "bidirectional"))
    )
    (net (code "93") (name "unconnected-(STM32A-PC12-Pad80)") (class "Default")
      (node (ref "STM32") (pin "80") (pinfunction "PC12_80") (pintype "bidirectional"))
    )
    (net (code "94") (name "unconnected-(STM32A-PC14-OSC32_IN(PC14)-Pad8)") (class "Default")
      (node (ref "STM32") (pin "8") (pinfunction "PC14-OSC32_IN(PC14)_8") (pintype "bidirectional"))
    )
    (net (code "95") (name "unconnected-(STM32A-PC15-OSC32_OUT(PC15)-Pad9)") (class "Default")
      (node (ref "STM32") (pin "9") (pinfunction "PC15-OSC32_OUT(PC15)_9") (pintype "bidirectional"))
    )
    (net (code "96") (name "unconnected-(STM32A-PD2-Pad83)") (class "Default")
      (node (ref "STM32") (pin "83") (pinfunction "PD2_83") (pintype "bidirectional"))
    )
    (net (code "97") (name "unconnected-(STM32A-PD3-Pad84)") (class "Default")
      (node (ref "STM32") (pin "84") (pinfunction "PD3_84") (pintype "bidirectional"))
    )
    (net (code "98") (name "unconnected-(STM32A-PD4-Pad85)") (class "Default")
      (node (ref "STM32") (pin "85") (pinfunction "PD4_85") (pintype "bidirectional"))
    )
    (net (code "99") (name "unconnected-(STM32A-PD14-Pad61)") (class "Default")
      (node (ref "STM32") (pin "61") (pinfunction "PD14_61") (pintype "bidirectional"))
    )
    (net (code "100") (name "unconnected-(STM32A-PD15-Pad62)") (class "Default")
      (node (ref "STM32") (pin "62") (pinfunction "PD15_62") (pintype "bidirectional"))
    )
    (net (code "101") (name "unconnected-(STM32A-PE0-Pad97)") (class "Default")
      (node (ref "STM32") (pin "97") (pinfunction "PE0_97") (pintype "bidirectional"))
    )
    (net (code "102") (name "unconnected-(STM32A-PE1-Pad98)") (class "Default")
      (node (ref "STM32") (pin "98") (pinfunction "PE1_98") (pintype "bidirectional"))
    )
    (net (code "103") (name "unconnected-(STM32A-PE2-Pad1)") (class "Default")
      (node (ref "STM32") (pin "1") (pinfunction "PE2_1") (pintype "bidirectional"))
    )
    (net (code "104") (name "unconnected-(STM32A-PE3-Pad2)") (class "Default")
      (node (ref "STM32") (pin "2") (pinfunction "PE3_2") (pintype "bidirectional"))
    )
    (net (code "105") (name "unconnected-(STM32A-PE4-Pad3)") (class "Default")
      (node (ref "STM32") (pin "3") (pinfunction "PE4_3") (pintype "bidirectional"))
    )
    (net (code "106") (name "unconnected-(STM32A-PE5-Pad4)") (class "Default")
      (node (ref "STM32") (pin "4") (pinfunction "PE5_4") (pintype "bidirectional"))
    )
    (net (code "107") (name "unconnected-(STM32A-PE6-Pad5)") (class "Default")
      (node (ref "STM32") (pin "5") (pinfunction "PE6_5") (pintype "bidirectional"))
    )
    (net (code "108") (name "unconnected-(STM32A-PE7-Pad38)") (class "Default")
      (node (ref "STM32") (pin "38") (pinfunction "PE7_38") (pintype "bidirectional+no_connect"))
    )
    (net (code "109") (name "unconnected-(STM32A-PE9-Pad40)") (class "Default")
      (node (ref "STM32") (pin "40") (pinfunction "PE9_40") (pintype "bidirectional+no_connect"))
    )
  )
)
